# SCH_Hackpad_2024-10-25.net
KiCad netlist of a schematic drawn in EasyEDA
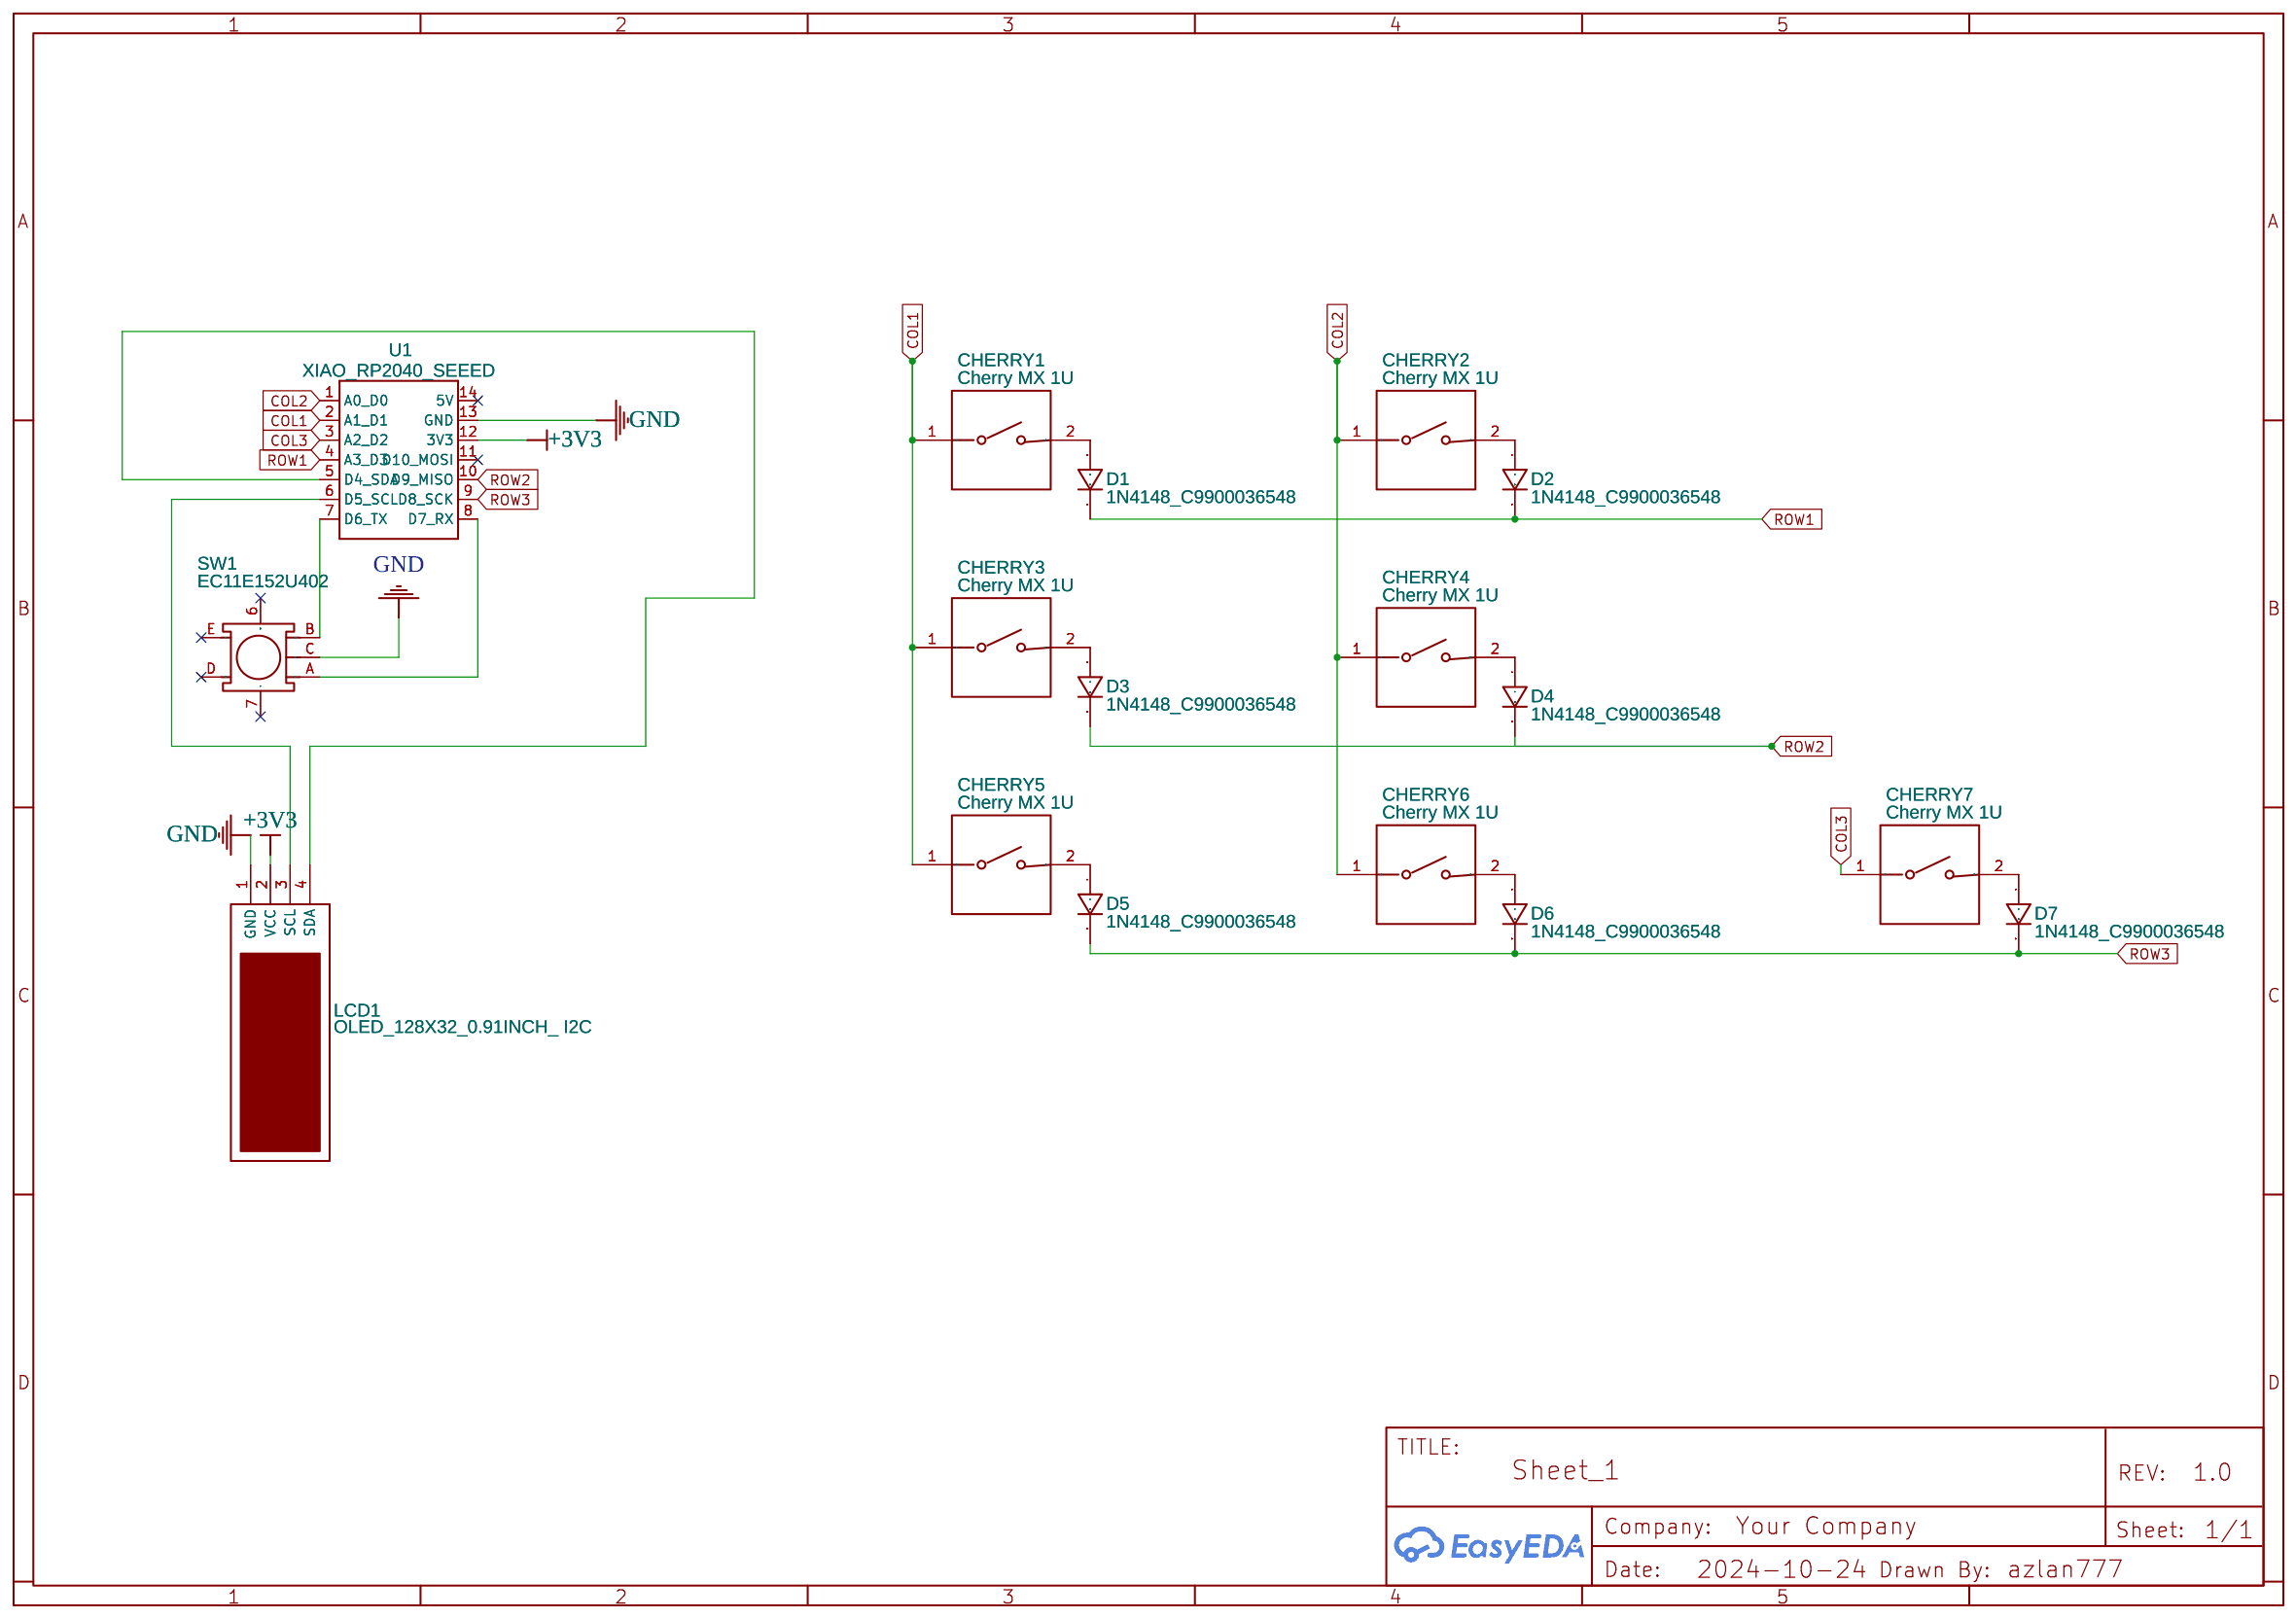
[diagram p0: schematic sheet]

(export (version "E")
  (design (tool "Eeschema 10.0.6"))
  (components
    (comp (ref "CHERRY1") (value "Cherry MX 1U") (libsource (lib "") (part "Cherry MX 1U")))
    (comp (ref "CHERRY2") (value "Cherry MX 1U") (libsource (lib "") (part "Cherry MX 1U")))
    (comp (ref "CHERRY3") (value "Cherry MX 1U") (libsource (lib "") (part "Cherry MX 1U")))
    (comp (ref "CHERRY4") (value "Cherry MX 1U") (libsource (lib "") (part "Cherry MX 1U")))
    (comp (ref "CHERRY5") (value "Cherry MX 1U") (libsource (lib "") (part "Cherry MX 1U")))
    (comp (ref "CHERRY6") (value "Cherry MX 1U") (libsource (lib "") (part "Cherry MX 1U")))
    (comp (ref "CHERRY7") (value "Cherry MX 1U") (libsource (lib "") (part "Cherry MX 1U")))
    (comp (ref "D1")
      (value "1N4148_C9900036548")
      (fields (field (name "Manufacturer Part") "1N4148"))
      (libsource (lib "") (part "1N4148_C9900036548"))
    )
    (comp (ref "D2")
      (value "1N4148_C9900036548")
      (fields (field (name "Manufacturer Part") "1N4148"))
      (libsource (lib "") (part "1N4148_C9900036548"))
    )
    (comp (ref "D3")
      (value "1N4148_C9900036548")
      (fields (field (name "Manufacturer Part") "1N4148"))
      (libsource (lib "") (part "1N4148_C9900036548"))
    )
    (comp (ref "D4")
      (value "1N4148_C9900036548")
      (fields (field (name "Manufacturer Part") "1N4148"))
      (libsource (lib "") (part "1N4148_C9900036548"))
    )
    (comp (ref "D5")
      (value "1N4148_C9900036548")
      (fields (field (name "Manufacturer Part") "1N4148"))
      (libsource (lib "") (part "1N4148_C9900036548"))
    )
    (comp (ref "D6")
      (value "1N4148_C9900036548")
      (fields (field (name "Manufacturer Part") "1N4148"))
      (libsource (lib "") (part "1N4148_C9900036548"))
    )
    (comp (ref "D7")
      (value "1N4148_C9900036548")
      (fields (field (name "Manufacturer Part") "1N4148"))
      (libsource (lib "") (part "1N4148_C9900036548"))
    )
    (comp (ref "LCD1")
      (value "OLED_128X32_0.91INCH_ I2C")
      (libsource (lib "") (part "OLED_128X32_0.91INCH_ I2C"))
    )
    (comp (ref "SW1")
      (value "EC11E152U402")
      (fields (field (name "Manufacturer") "ALPSALPINE(阿尔卑斯阿尔派)"))
      (libsource (lib "") (part "EC11E152U402"))
    )
    (comp (ref "U1") (value "XIAO_RP2040_SEEED") (libsource (lib "") (part "XIAO_RP2040_SEEED")))
  )
  (nets
    (net (code "1") (name "+3V3") (class "Default")
      (node (ref "LCD1") (pin "2") (pinfunction "VCC_2") (pintype "passive"))
      (node (ref "U1") (pin "12") (pinfunction "3V3_12") (pintype "bidirectional"))
    )
    (net (code "2") (name "COL1") (class "Default")
      (node (ref "CHERRY1") (pin "1") (pinfunction "1_1") (pintype "unspecified"))
      (node (ref "CHERRY3") (pin "1") (pinfunction "1_1") (pintype "unspecified"))
      (node (ref "CHERRY5") (pin "1") (pinfunction "1_1") (pintype "unspecified"))
      (node (ref "U1") (pin "2") (pinfunction "A1_D1_2") (pintype "bidirectional"))
    )
    (net (code "3") (name "COL2") (class "Default")
      (node (ref "CHERRY2") (pin "1") (pinfunction "1_1") (pintype "unspecified"))
      (node (ref "CHERRY4") (pin "1") (pinfunction "1_1") (pintype "unspecified"))
      (node (ref "CHERRY6") (pin "1") (pinfunction "1_1") (pintype "unspecified"))
      (node (ref "U1") (pin "1") (pinfunction "A0_D0_1") (pintype "bidirectional"))
    )
    (net (code "4") (name "COL3") (class "Default")
      (node (ref "CHERRY7") (pin "1") (pinfunction "1_1") (pintype "unspecified"))
      (node (ref "U1") (pin "3") (pinfunction "A2_D2_3") (pintype "bidirectional"))
    )
    (net (code "5") (name "GND") (class "Default")
      (node (ref "LCD1") (pin "1") (pinfunction "GND_1") (pintype "passive"))
      (node (ref "SW1") (pin "C") (pinfunction "C_C") (pintype "unspecified"))
      (node (ref "U1") (pin "13") (pinfunction "GND_13") (pintype "bidirectional"))
    )
    (net (code "6") (name "Net-(D1-A)") (class "Default")
      (node (ref "CHERRY1") (pin "2") (pinfunction "2_2") (pintype "unspecified"))
      (node (ref "D1") (pin "1") (pinfunction "A_1") (pintype "unspecified"))
    )
    (net (code "7") (name "Net-(D2-A)") (class "Default")
      (node (ref "CHERRY2") (pin "2") (pinfunction "2_2") (pintype "unspecified"))
      (node (ref "D2") (pin "1") (pinfunction "A_1") (pintype "unspecified"))
    )
    (net (code "8") (name "Net-(D3-A)") (class "Default")
      (node (ref "CHERRY3") (pin "2") (pinfunction "2_2") (pintype "unspecified"))
      (node (ref "D3") (pin "1") (pinfunction "A_1") (pintype "unspecified"))
    )
    (net (code "9") (name "Net-(D4-A)") (class "Default")
      (node (ref "CHERRY4") (pin "2") (pinfunction "2_2") (pintype "unspecified"))
      (node (ref "D4") (pin "1") (pinfunction "A_1") (pintype "unspecified"))
    )
    (net (code "10") (name "Net-(D5-A)") (class "Default")
      (node (ref "CHERRY5") (pin "2") (pinfunction "2_2") (pintype "unspecified"))
      (node (ref "D5") (pin "1") (pinfunction "A_1") (pintype "unspecified"))
    )
    (net (code "11") (name "Net-(D6-A)") (class "Default")
      (node (ref "CHERRY6") (pin "2") (pinfunction "2_2") (pintype "unspecified"))
      (node (ref "D6") (pin "1") (pinfunction "A_1") (pintype "unspecified"))
    )
    (net (code "12") (name "Net-(D7-A)") (class "Default")
      (node (ref "CHERRY7") (pin "2") (pinfunction "2_2") (pintype "unspecified"))
      (node (ref "D7") (pin "1") (pinfunction "A_1") (pintype "unspecified"))
    )
    (net (code "13") (name "Net-(LCD1-SCL)") (class "Default")
      (node (ref "LCD1") (pin "3") (pinfunction "SCL_3") (pintype "input"))
      (node (ref "U1") (pin "6") (pinfunction "D5_SCL_6") (pintype "bidirectional"))
    )
    (net (code "14") (name "Net-(LCD1-SDA)") (class "Default")
      (node (ref "LCD1") (pin "4") (pinfunction "SDA_4") (pintype "bidirectional"))
      (node (ref "U1") (pin "5") (pinfunction "D4_SDA_5") (pintype "bidirectional"))
    )
    (net (code "15") (name "Net-(U1-D6_TX)") (class "Default")
      (node (ref "SW1") (pin "B") (pinfunction "B_B") (pintype "unspecified"))
      (node (ref "U1") (pin "7") (pinfunction "D6_TX_7") (pintype "bidirectional"))
    )
    (net (code "16") (name "Net-(U1-D7_RX)") (class "Default")
      (node (ref "SW1") (pin "A") (pinfunction "A_A") (pintype "unspecified"))
      (node (ref "U1") (pin "8") (pinfunction "D7_RX_8") (pintype "bidirectional"))
    )
    (net (code "17") (name "ROW1") (class "Default")
      (node (ref "D1") (pin "2") (pinfunction "C_2") (pintype "unspecified"))
      (node (ref "D2") (pin "2") (pinfunction "C_2") (pintype "unspecified"))
      (node (ref "U1") (pin "4") (pinfunction "A3_D3_4") (pintype "bidirectional"))
    )
    (net (code "18") (name "ROW2") (class "Default")
      (node (ref "D3") (pin "2") (pinfunction "C_2") (pintype "unspecified"))
      (node (ref "D4") (pin "2") (pinfunction "C_2") (pintype "unspecified"))
      (node (ref "U1") (pin "10") (pinfunction "D9_MISO_10") (pintype "bidirectional"))
    )
    (net (code "19") (name "ROW3") (class "Default")
      (node (ref "D5") (pin "2") (pinfunction "C_2") (pintype "unspecified"))
      (node (ref "D6") (pin "2") (pinfunction "C_2") (pintype "unspecified"))
      (node (ref "D7") (pin "2") (pinfunction "C_2") (pintype "unspecified"))
      (node (ref "U1") (pin "9") (pinfunction "D8_SCK_9") (pintype "bidirectional"))
    )
    (net (code "20") (name "unconnected-(SW1-Pad6)") (class "Default")
      (node (ref "SW1") (pin "6") (pinfunction "6_6") (pintype "unspecified+no_connect"))
    )
    (net (code "21") (name "unconnected-(SW1-Pad7)") (class "Default")
      (node (ref "SW1") (pin "7") (pinfunction "7_7") (pintype "unspecified+no_connect"))
    )
    (net (code "22") (name "unconnected-(SW1-PadD)") (class "Default")
      (node (ref "SW1") (pin "D") (pinfunction "D_D") (pintype "unspecified+no_connect"))
    )
    (net (code "23") (name "unconnected-(SW1-PadE)") (class "Default")
      (node (ref "SW1") (pin "E") (pinfunction "E_E") (pintype "unspecified+no_connect"))
    )
    (net (code "24") (name "unconnected-(U1-5V-Pad14)") (class "Default")
      (node (ref "U1") (pin "14") (pinfunction "5V_14") (pintype "bidirectional+no_connect"))
    )
    (net (code "25") (name "unconnected-(U1-D10_MOSI-Pad11)") (class "Default")
      (node (ref "U1") (pin "11") (pinfunction "D10_MOSI_11") (pintype "bidirectional+no_connect"))
    )
  )
)
